# RFID_Reader_Writer.net
KiCad netlist of a schematic drawn in Altium Designer
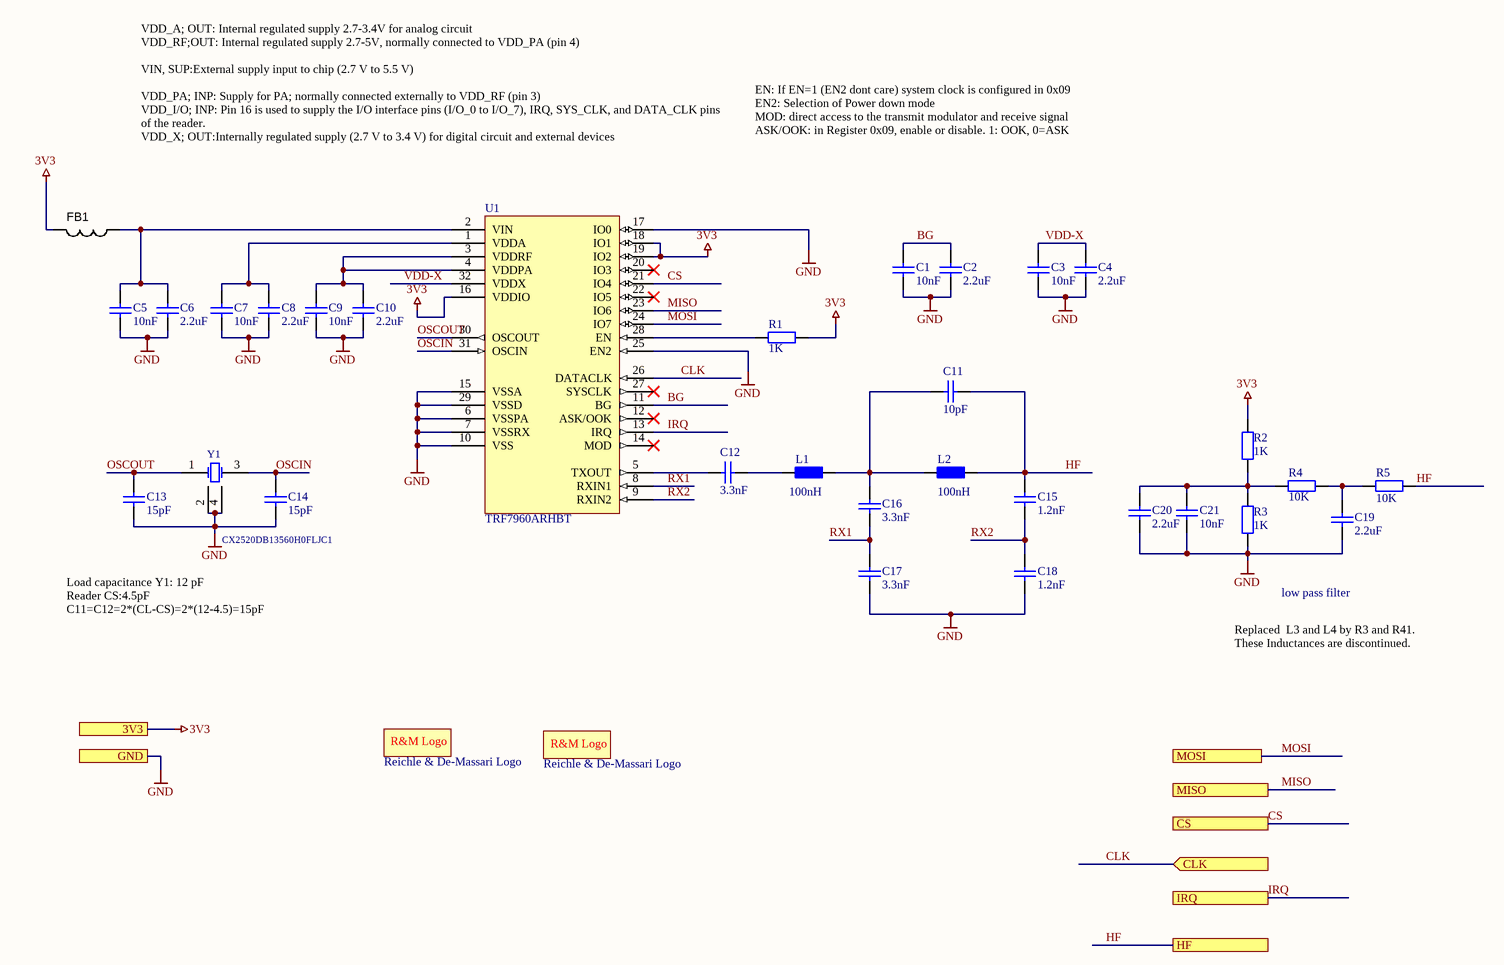
[diagram p0: RFID_Reader_Writer.SchDoc]

(export (version "E")
  (design (tool "Eeschema 10.0.6"))
  (components
    (comp (ref "*1")
      (value "Reichle & De-Massari Logo")
      (footprint "SYMBOL_R&M")
      (libsource (lib "RDM_ALT_SCH") (part "SYMBOL_R&M"))
    )
    (comp (ref "*2")
      (value "Reichle & De-Massari Logo")
      (footprint "SYMBOL_R&M")
      (libsource (lib "RDM_ALT_SCH") (part "SYMBOL_R&M"))
    )
    (comp (ref "C1")
      (value "10nF")
      (footprint "Ceramic Capacitor 0402 EIA")
      (description "10000pF ±10% 50V Keramikkondensatoren X7R 0402 (1005 metrisch) CL05B103KB5NNNC")
      (fields (field (name "TOLERANCE") "±10%") (field (name "VOLTAGE") "50 VDC"))
      (libsource (lib "RDM_ALT_SCH") (part "Cap_10nF_0402"))
    )
    (comp (ref "C2")
      (value "2.2uF")
      (footprint "Ceramic Capacitor 0402 EIA")
      (fields
        (field (name "TOLERANCE") "±20%")
        (field (name "VOLTAGE") "6,3V")
        (field (name "MANUFACTURER") "Murata")
      )
      (libsource (lib "RDM_ALT_SCH") (part "Cap_2.2uF_0402"))
    )
    (comp (ref "C3")
      (value "10nF")
      (footprint "Ceramic Capacitor 0402 EIA")
      (description "10000pF ±10% 50V Keramikkondensatoren X7R 0402 (1005 metrisch) CL05B103KB5NNNC")
      (fields (field (name "TOLERANCE") "±10%") (field (name "VOLTAGE") "50 VDC"))
      (libsource (lib "RDM_ALT_SCH") (part "Cap_10nF_0402"))
    )
    (comp (ref "C4")
      (value "2.2uF")
      (footprint "Ceramic Capacitor 0402 EIA")
      (fields
        (field (name "TOLERANCE") "±20%")
        (field (name "VOLTAGE") "6,3V")
        (field (name "MANUFACTURER") "Murata")
      )
      (libsource (lib "RDM_ALT_SCH") (part "Cap_2.2uF_0402"))
    )
    (comp (ref "C5")
      (value "10nF")
      (footprint "Ceramic Capacitor 0402 EIA")
      (description "10000pF ±10% 50V Keramikkondensatoren X7R 0402 (1005 metrisch) CL05B103KB5NNNC")
      (fields (field (name "TOLERANCE") "±10%") (field (name "VOLTAGE") "50 VDC"))
      (libsource (lib "RDM_ALT_SCH") (part "Cap_10nF_0402"))
    )
    (comp (ref "C6")
      (value "2.2uF")
      (footprint "Ceramic Capacitor 0402 EIA")
      (fields
        (field (name "TOLERANCE") "±20%")
        (field (name "VOLTAGE") "6,3V")
        (field (name "MANUFACTURER") "Murata")
      )
      (libsource (lib "RDM_ALT_SCH") (part "Cap_2.2uF_0402"))
    )
    (comp (ref "C7")
      (value "10nF")
      (footprint "Ceramic Capacitor 0402 EIA")
      (description "10000pF ±10% 50V Keramikkondensatoren X7R 0402 (1005 metrisch) CL05B103KB5NNNC")
      (fields (field (name "TOLERANCE") "±10%") (field (name "VOLTAGE") "50 VDC"))
      (libsource (lib "RDM_ALT_SCH") (part "Cap_10nF_0402"))
    )
    (comp (ref "C8")
      (value "2.2uF")
      (footprint "Ceramic Capacitor 0402 EIA")
      (fields
        (field (name "TOLERANCE") "±20%")
        (field (name "VOLTAGE") "6,3V")
        (field (name "MANUFACTURER") "Murata")
      )
      (libsource (lib "RDM_ALT_SCH") (part "Cap_2.2uF_0402"))
    )
    (comp (ref "C9")
      (value "10nF")
      (footprint "Ceramic Capacitor 0402 EIA")
      (description "10000pF ±10% 50V Keramikkondensatoren X7R 0402 (1005 metrisch) CL05B103KB5NNNC")
      (fields (field (name "TOLERANCE") "±10%") (field (name "VOLTAGE") "50 VDC"))
      (libsource (lib "RDM_ALT_SCH") (part "Cap_10nF_0402"))
    )
    (comp (ref "C10")
      (value "2.2uF")
      (footprint "Ceramic Capacitor 0402 EIA")
      (fields
        (field (name "TOLERANCE") "±20%")
        (field (name "VOLTAGE") "6,3V")
        (field (name "MANUFACTURER") "Murata")
      )
      (libsource (lib "RDM_ALT_SCH") (part "Cap_2.2uF_0402"))
    )
    (comp (ref "C11")
      (value "10pF")
      (footprint "Ceramic Capacitor 0402 EIA")
      (description "Multilayer Ceramic Capacitors MLCC - SMD/SMT 0402 10pF 50Volts C0G 1%")
      (fields (field (name "TOLERANCE") "±1%") (field (name "VOLTAGE") "50 VDC"))
      (libsource (lib "RDM_ALT_SCH") (part "Cap_10pF_0402"))
    )
    (comp (ref "C12")
      (value "3.3nF")
      (footprint "Ceramic Capacitor 0402 EIA")
      (description "Multilayer Ceramic Capacitors MLCC - SMD/SMT 0402 3300pF 50volts X7R 5%")
      (fields (field (name "TOLERANCE") "±5%") (field (name "VOLTAGE") "50 VDC"))
      (libsource (lib "RDM_ALT_SCH") (part "Cap_3.3nF_0402"))
    )
    (comp (ref "C13")
      (value "15pF")
      (footprint "Ceramic Capacitor 0402 EIA")
      (fields
        (field (name "TOLERANCE") "±1%")
        (field (name "VOLTAGE") "50 VDC")
        (field (name "MANUFACTURER") "Murata")
      )
      (libsource (lib "RDM_ALT_SCH") (part "Cap_15pF_0402"))
    )
    (comp (ref "C14")
      (value "15pF")
      (footprint "Ceramic Capacitor 0402 EIA")
      (fields
        (field (name "TOLERANCE") "±1%")
        (field (name "VOLTAGE") "50 VDC")
        (field (name "MANUFACTURER") "Murata")
      )
      (libsource (lib "RDM_ALT_SCH") (part "Cap_15pF_0402"))
    )
    (comp (ref "C15")
      (value "1.2nF")
      (footprint "Ceramic Capacitor 0402 EIA")
      (description "Multilayer Ceramic Capacitors MLCC - SMD/SMT 50V 1200pF C0G 0402 5%")
      (fields (field (name "TOLERANCE") "±5%") (field (name "VOLTAGE") "50 VDC"))
      (libsource (lib "RDM_ALT_SCH") (part "Cap_1.2nF_0402"))
    )
    (comp (ref "C16")
      (value "3.3nF")
      (footprint "Ceramic Capacitor 0402 EIA")
      (description "Multilayer Ceramic Capacitors MLCC - SMD/SMT 0402 3300pF 50volts X7R 5%")
      (fields (field (name "TOLERANCE") "±5%") (field (name "VOLTAGE") "50 VDC"))
      (libsource (lib "RDM_ALT_SCH") (part "Cap_3.3nF_0402"))
    )
    (comp (ref "C17")
      (value "3.3nF")
      (footprint "Ceramic Capacitor 0402 EIA")
      (description "Multilayer Ceramic Capacitors MLCC - SMD/SMT 0402 3300pF 50volts X7R 5%")
      (fields (field (name "TOLERANCE") "±5%") (field (name "VOLTAGE") "50 VDC"))
      (libsource (lib "RDM_ALT_SCH") (part "Cap_3.3nF_0402"))
    )
    (comp (ref "C18")
      (value "1.2nF")
      (footprint "Ceramic Capacitor 0402 EIA")
      (description "Multilayer Ceramic Capacitors MLCC - SMD/SMT 50V 1200pF C0G 0402 5%")
      (fields (field (name "TOLERANCE") "±5%") (field (name "VOLTAGE") "50 VDC"))
      (libsource (lib "RDM_ALT_SCH") (part "Cap_1.2nF_0402"))
    )
    (comp (ref "C19")
      (value "2.2uF")
      (footprint "Ceramic Capacitor 0402 EIA")
      (description "Multilayer Ceramic Capacitors MLCC - SMD/SMT 0402 2.2uF 6.3volts")
      (fields (field (name "TOLERANCE") "20%") (field (name "VOLTAGE") "6.3V"))
      (libsource (lib "RDM_ALT_SCH") (part "Cap_2.2uF_0402_6.3V"))
    )
    (comp (ref "C20")
      (value "2.2uF")
      (footprint "Ceramic Capacitor 0402 EIA")
      (description "Multilayer Ceramic Capacitors MLCC - SMD/SMT 0402 2.2uF 6.3volts")
      (fields (field (name "TOLERANCE") "20%") (field (name "VOLTAGE") "6.3V"))
      (libsource (lib "RDM_ALT_SCH") (part "Cap_2.2uF_0402_6.3V"))
    )
    (comp (ref "C21")
      (value "10nF")
      (footprint "Ceramic Capacitor 0402 EIA")
      (description "10000pF ±10% 50V Keramikkondensatoren X7R 0402 (1005 metrisch) CL05B103KB5NNNC")
      (fields (field (name "TOLERANCE") "±10%") (field (name "VOLTAGE") "50 VDC"))
      (libsource (lib "RDM_ALT_SCH") (part "Cap_10nF_0402"))
    )
    (comp (ref "FB1")
      (value "BK1005HS102-T")
      (footprint "CAPC1005X55N")
      (description "FERRITE BEAD 1 KOHM 0402 1LN")
      (fields (field (name "MANUFACTURER") "Taiyo Yuden"))
      (libsource (lib "PBL - Inductors") (part "FERRITE_2K2-100MHz_0603"))
    )
    (comp (ref "L1")
      (value "100nH")
      (footprint "Inductor 0603 EIA")
      (description "100nH Unshielded Multilayer Inductor 300mA 100 mOhm Max 0603 (1608 Metric)")
      (fields (field (name "MANUFACTURER") "Taiyo Yuden") (field (name "Comment") "HK1608R10J-T"))
      (libsource (lib "altium-import") (part "root_0_706xx_R+M_InteliPhyII_KTI-00029-A.1_"))
    )
    (comp (ref "L2")
      (value "100nH")
      (footprint "Inductor 0603 EIA")
      (description "100nH Unshielded Multilayer Inductor 300mA 100 mOhm Max 0603 (1608 Metric)")
      (fields (field (name "MANUFACTURER") "Taiyo Yuden") (field (name "Comment") "HK1608R10J-T"))
      (libsource (lib "altium-import") (part "root_0_706xx_R+M_InteliPhyII_KTI-00029-A.1_"))
    )
    (comp (ref "R1")
      (value "1K")
      (footprint "Resistor 0402 EIA")
      (description "RES SMD 1K OHM 1% 1/16W 0402")
      (fields (field (name "TOLERANCE") "±1%") (field (name "POWER") "0,063W, 1/16W"))
      (libsource (lib "") (part "Res_1K_0402_1"))
    )
    (comp (ref "R2")
      (value "1K")
      (footprint "Resistor 0402 EIA")
      (description "RES SMD 1K OHM 1% 1/16W 0402")
      (fields (field (name "TOLERANCE") "±1%") (field (name "POWER") "0,063W, 1/16W"))
      (libsource (lib "RDM_ALT_SCH") (part "Res_1K_0402"))
    )
    (comp (ref "R3")
      (value "1K")
      (footprint "Resistor 0402 EIA")
      (description "RES SMD 1K OHM 1% 1/16W 0402")
      (fields (field (name "TOLERANCE") "±1%") (field (name "POWER") "0,063W, 1/16W"))
      (libsource (lib "RDM_ALT_SCH") (part "Res_1K_0402"))
    )
    (comp (ref "R4")
      (value "10K")
      (footprint "Resistor 0402 EIA")
      (description "SMD 10K ohm 1% 50V General Purpose")
      (fields (field (name "TOLERANCE") "1%") (field (name "POWER") "63mW"))
      (libsource (lib "RDM_ALT_SCH") (part "Res_10K_0402"))
    )
    (comp (ref "R5")
      (value "10K")
      (footprint "Resistor 0402 EIA")
      (description "SMD 10K ohm 1% 50V General Purpose")
      (fields (field (name "TOLERANCE") "1%") (field (name "POWER") "63mW"))
      (libsource (lib "RDM_ALT_SCH") (part "Res_10K_0402"))
    )
    (comp (ref "U1")
      (value "TRF7960ARHBT")
      (footprint "TexasInstruments_32-VFQFN_32_R")
      (fields (field (name "MANUFACTURER") "Texas Instruments"))
      (libsource (lib "RDM_Altium_Library") (part "TexasInstruments_TRF7960ARHBT_32-VFQFN_32"))
    )
    (comp (ref "Y1")
      (value "CX2520DB13560H0FLJC1")
      (footprint "AVX/Kyocera_DFN4_4_RWH")
      (description "13.56MHz ±10ppm Crystal 12pF 150 Ohms 4-SMD, No Lead")
      (fields (field (name "MANUFACTURER") "Kyocera International Inc. Electronic Components"))
      (libsource (lib "RDM_Altium_Library") (part "CRYSTAL_4Pin_1_3_1"))
    )
  )
  (nets
    (net (code "1") (name "/BG") (class "Default")
      (node (ref "C1") (pin "2") (pinfunction "2_2") (pintype "passive"))
      (node (ref "C2") (pin "2") (pinfunction "2_2") (pintype "passive"))
      (node (ref "U1") (pin "11") (pinfunction "BG_11") (pintype "output"))
    )
    (net (code "2") (name "/CLK") (class "Default")
      (node (ref "U1") (pin "26") (pinfunction "DATACLK_26") (pintype "input"))
    )
    (net (code "3") (name "/CS") (class "Default")
      (node (ref "U1") (pin "21") (pinfunction "IO4_21") (pintype "bidirectional"))
    )
    (net (code "4") (name "/HF") (class "Default")
      (node (ref "C11") (pin "1") (pinfunction "1_1") (pintype "passive"))
      (node (ref "C15") (pin "2") (pinfunction "2_2") (pintype "passive"))
      (node (ref "L2") (pin "2") (pinfunction "2_2") (pintype "passive"))
      (node (ref "R5") (pin "2") (pinfunction "2_2") (pintype "passive"))
    )
    (net (code "5") (name "/IRQ") (class "Default")
      (node (ref "U1") (pin "13") (pinfunction "IRQ_13") (pintype "output"))
    )
    (net (code "6") (name "/MISO") (class "Default")
      (node (ref "U1") (pin "23") (pinfunction "IO6_23") (pintype "bidirectional"))
    )
    (net (code "7") (name "/MOSI") (class "Default")
      (node (ref "U1") (pin "24") (pinfunction "IO7_24") (pintype "bidirectional"))
    )
    (net (code "8") (name "/OSCIN") (class "Default")
      (node (ref "C14") (pin "2") (pinfunction "2_2") (pintype "passive"))
      (node (ref "U1") (pin "31") (pinfunction "OSCIN_31") (pintype "input"))
      (node (ref "Y1") (pin "3") (pinfunction "OSC2_3") (pintype "passive"))
    )
    (net (code "9") (name "/OSCOUT") (class "Default")
      (node (ref "C13") (pin "2") (pinfunction "2_2") (pintype "passive"))
      (node (ref "U1") (pin "30") (pinfunction "OSCOUT_30") (pintype "output"))
      (node (ref "Y1") (pin "1") (pinfunction "OSC1_1") (pintype "passive"))
    )
    (net (code "10") (name "/RX1") (class "Default")
      (node (ref "C16") (pin "1") (pinfunction "1_1") (pintype "passive"))
      (node (ref "C17") (pin "2") (pinfunction "2_2") (pintype "passive"))
      (node (ref "U1") (pin "8") (pinfunction "RXIN1_8") (pintype "input"))
    )
    (net (code "11") (name "/RX2") (class "Default")
      (node (ref "C15") (pin "1") (pinfunction "1_1") (pintype "passive"))
      (node (ref "C18") (pin "2") (pinfunction "2_2") (pintype "passive"))
      (node (ref "U1") (pin "9") (pinfunction "RXIN2_9") (pintype "input"))
    )
    (net (code "12") (name "/VDD-X") (class "Default")
      (node (ref "C3") (pin "2") (pinfunction "2_2") (pintype "passive"))
      (node (ref "C4") (pin "2") (pinfunction "2_2") (pintype "passive"))
      (node (ref "U1") (pin "32") (pinfunction "VDDX_32") (pintype "power_in"))
    )
    (net (code "13") (name "3V3") (class "Default")
      (node (ref "FB1") (pin "2") (pinfunction "2_2") (pintype "passive"))
      (node (ref "R1") (pin "2") (pinfunction "2_2") (pintype "passive"))
      (node (ref "R2") (pin "1") (pinfunction "1_1") (pintype "passive"))
      (node (ref "U1") (pin "16") (pinfunction "VDDIO_16") (pintype "power_in"))
      (node (ref "U1") (pin "18") (pinfunction "IO1_18") (pintype "bidirectional"))
      (node (ref "U1") (pin "19") (pinfunction "IO2_19") (pintype "bidirectional"))
    )
    (net (code "14") (name "GND") (class "Default")
      (node (ref "C1") (pin "1") (pinfunction "1_1") (pintype "passive"))
      (node (ref "C10") (pin "1") (pinfunction "1_1") (pintype "passive"))
      (node (ref "C13") (pin "1") (pinfunction "1_1") (pintype "passive"))
      (node (ref "C14") (pin "1") (pinfunction "1_1") (pintype "passive"))
      (node (ref "C17") (pin "1") (pinfunction "1_1") (pintype "passive"))
      (node (ref "C18") (pin "1") (pinfunction "1_1") (pintype "passive"))
      (node (ref "C19") (pin "1") (pinfunction "1_1") (pintype "passive"))
      (node (ref "C2") (pin "1") (pinfunction "1_1") (pintype "passive"))
      (node (ref "C20") (pin "1") (pinfunction "1_1") (pintype "passive"))
      (node (ref "C21") (pin "1") (pinfunction "1_1") (pintype "passive"))
      (node (ref "C3") (pin "1") (pinfunction "1_1") (pintype "passive"))
      (node (ref "C4") (pin "1") (pinfunction "1_1") (pintype "passive"))
      (node (ref "C5") (pin "1") (pinfunction "1_1") (pintype "passive"))
      (node (ref "C6") (pin "1") (pinfunction "1_1") (pintype "passive"))
      (node (ref "C7") (pin "1") (pinfunction "1_1") (pintype "passive"))
      (node (ref "C8") (pin "1") (pinfunction "1_1") (pintype "passive"))
      (node (ref "C9") (pin "1") (pinfunction "1_1") (pintype "passive"))
      (node (ref "R3") (pin "2") (pinfunction "2_2") (pintype "passive"))
      (node (ref "U1") (pin "10") (pinfunction "VSS_10") (pintype "passive"))
      (node (ref "U1") (pin "15") (pinfunction "VSSA_15") (pintype "passive"))
      (node (ref "U1") (pin "17") (pinfunction "IO0_17") (pintype "bidirectional"))
      (node (ref "U1") (pin "25") (pinfunction "EN2_25") (pintype "input"))
      (node (ref "U1") (pin "29") (pinfunction "VSSD_29") (pintype "passive"))
      (node (ref "U1") (pin "6") (pinfunction "VSSPA_6") (pintype "passive"))
      (node (ref "U1") (pin "7") (pinfunction "VSSRX_7") (pintype "passive"))
      (node (ref "Y1") (pin "2") (pinfunction "OSC2_2") (pintype "passive"))
      (node (ref "Y1") (pin "4") (pinfunction "OSC3_4") (pintype "passive"))
    )
    (net (code "15") (name "Net-(C11-Pad2)") (class "Default")
      (node (ref "C11") (pin "2") (pinfunction "2_2") (pintype "passive"))
      (node (ref "C16") (pin "2") (pinfunction "2_2") (pintype "passive"))
      (node (ref "L1") (pin "2") (pinfunction "2_2") (pintype "passive"))
      (node (ref "L2") (pin "1") (pinfunction "1_1") (pintype "passive"))
    )
    (net (code "16") (name "Net-(C12-Pad1)") (class "Default")
      (node (ref "C12") (pin "1") (pinfunction "1_1") (pintype "passive"))
      (node (ref "L1") (pin "1") (pinfunction "1_1") (pintype "passive"))
    )
    (net (code "17") (name "Net-(C19-Pad2)") (class "Default")
      (node (ref "C19") (pin "2") (pinfunction "2_2") (pintype "passive"))
      (node (ref "R4") (pin "2") (pinfunction "2_2") (pintype "passive"))
      (node (ref "R5") (pin "1") (pinfunction "1_1") (pintype "passive"))
    )
    (net (code "18") (name "Net-(C20-Pad2)") (class "Default")
      (node (ref "C20") (pin "2") (pinfunction "2_2") (pintype "passive"))
      (node (ref "C21") (pin "2") (pinfunction "2_2") (pintype "passive"))
      (node (ref "R2") (pin "2") (pinfunction "2_2") (pintype "passive"))
      (node (ref "R3") (pin "1") (pinfunction "1_1") (pintype "passive"))
      (node (ref "R4") (pin "1") (pinfunction "1_1") (pintype "passive"))
    )
    (net (code "19") (name "Net-(U1-EN)") (class "Default")
      (node (ref "R1") (pin "1") (pinfunction "1_1") (pintype "passive"))
      (node (ref "U1") (pin "28") (pinfunction "EN_28") (pintype "input"))
    )
    (net (code "20") (name "Net-(U1-TXOUT)") (class "Default")
      (node (ref "C12") (pin "2") (pinfunction "2_2") (pintype "passive"))
      (node (ref "U1") (pin "5") (pinfunction "TXOUT_5") (pintype "output"))
    )
    (net (code "21") (name "Net-(U1-VDDA)") (class "Default")
      (node (ref "C7") (pin "2") (pinfunction "2_2") (pintype "passive"))
      (node (ref "C8") (pin "2") (pinfunction "2_2") (pintype "passive"))
      (node (ref "U1") (pin "1") (pinfunction "VDDA_1") (pintype "power_in"))
    )
    (net (code "22") (name "Net-(U1-VDDPA)") (class "Default")
      (node (ref "C10") (pin "2") (pinfunction "2_2") (pintype "passive"))
      (node (ref "C9") (pin "2") (pinfunction "2_2") (pintype "passive"))
      (node (ref "U1") (pin "3") (pinfunction "VDDRF_3") (pintype "power_in"))
      (node (ref "U1") (pin "4") (pinfunction "VDDPA_4") (pintype "power_in"))
    )
    (net (code "23") (name "Net-(U1-VIN)") (class "Default")
      (node (ref "C5") (pin "2") (pinfunction "2_2") (pintype "passive"))
      (node (ref "C6") (pin "2") (pinfunction "2_2") (pintype "passive"))
      (node (ref "FB1") (pin "1") (pinfunction "1_1") (pintype "passive"))
      (node (ref "U1") (pin "2") (pinfunction "VIN_2") (pintype "power_in"))
    )
    (net (code "24") (name "unconnected-(U1-ASK{slash}OOK-Pad12)") (class "Default")
      (node (ref "U1") (pin "12") (pinfunction "ASK/OOK_12") (pintype "output+no_connect"))
    )
    (net (code "25") (name "unconnected-(U1-IO3-Pad20)") (class "Default")
      (node (ref "U1") (pin "20") (pinfunction "IO3_20") (pintype "bidirectional+no_connect"))
    )
    (net (code "26") (name "unconnected-(U1-IO5-Pad22)") (class "Default")
      (node (ref "U1") (pin "22") (pinfunction "IO5_22") (pintype "bidirectional+no_connect"))
    )
    (net (code "27") (name "unconnected-(U1-MOD-Pad14)") (class "Default")
      (node (ref "U1") (pin "14") (pinfunction "MOD_14") (pintype "output+no_connect"))
    )
    (net (code "28") (name "unconnected-(U1-SYSCLK-Pad27)") (class "Default")
      (node (ref "U1") (pin "27") (pinfunction "SYSCLK_27") (pintype "output+no_connect"))
    )
  )
)
